# 26D_STEPPER_test.net
KiCad netlist of a schematic drawn in Altium Designer
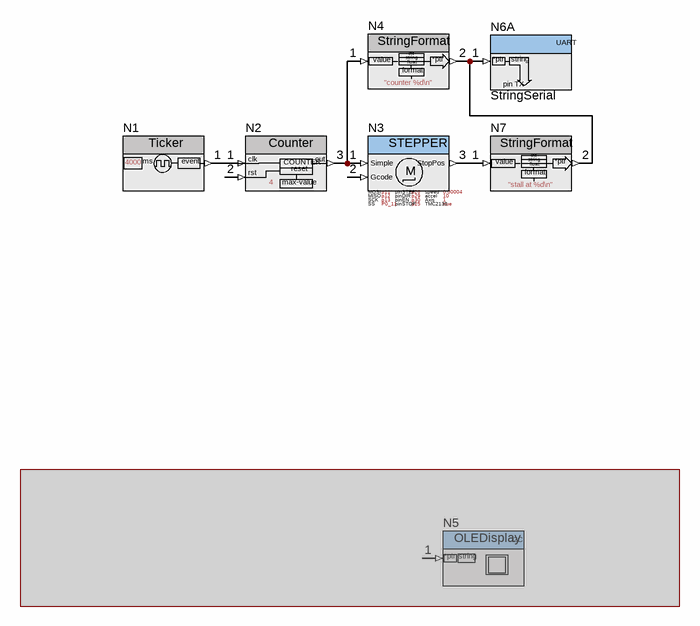
[diagram p0: 26D_STEPPER_test.SchDoc]

(export (version "E")
  (design (tool "Eeschema 10.0.6"))
  (components
    (comp (ref "N1")
      (value "Ticker")
      (description "Creates a Periodical Event")
      (fields (field (name "NBLOCKSPARAMETER1") "4000"))
      (libsource (lib "studio") (part "NODE-TICKER"))
    )
    (comp (ref "N2")
      (value "Counter")
      (fields (field (name "NBLOCKSPARAMETER1") "4"))
      (libsource (lib "studio") (part "NODE-COUNTER"))
    )
    (comp (ref "N3")
      (value "STEPPER")
      (fields
        (field (name "NBLOCKSPARAMETER7") "p30")
        (field (name "NBLOCKSPARAMETER8") "p25")
        (field (name "NBLOCKSPARAMETER9") "0.00004")
        (field (name "NBLOCKSPARAMETER10") "10")
        (field (name "NBLOCKSPARAMETER11") "1")
        (field (name "NBLOCKSPARAMETER12") "true")
        (field (name "PARAMETER 12") "TMC2130")
        (field (name "PARAMETER 11") "Axis")
        (field (name "PARAMETER 10") "accel")
        (field (name "PARAMETER 9") "speed")
        (field (name "PARAMETER 8") "pinSTOP")
        (field (name "PARAMETER 7") "pinEN")
        (field (name "NBLOCKSPARAMETER1") "p11")
        (field (name "NBLOCKSPARAMETER2") "p12")
        (field (name "NBLOCKSPARAMETER3") "p13")
        (field (name "NBLOCKSPARAMETER4") "P0_11")
        (field (name "NBLOCKSPARAMETER5") "p26")
        (field (name "NBLOCKSPARAMETER6") "p29")
        (field (name "PARAMETER 6") "pinDIR")
        (field (name "PARAMETER 5") "pinSTEP")
        (field (name "PARAMETER 2") "MISO")
        (field (name "PARAMETER 1") "MOSI")
        (field (name "PARAMETER 4") "SS")
        (field (name "PARAMETER 3") "SCK")
      )
      (libsource (lib "studio") (part "NODE-STEPPER"))
    )
    (comp (ref "N4")
      (value "StringFormat")
      (fields (field (name "NBLOCKSPARAMETER1") "\"counter %~{d}n\""))
      (libsource (lib "studio") (part "NODE-STRINGFORMAT"))
    )
    (comp (ref "N5") (value "OLEDisplay") (libsource (lib "studio") (part "NODE-OLEDisplay")))
    (comp (ref "N6") (value "StringSerial") (libsource (lib "studio") (part "NODE-STRINGSERIAL-split")))
    (comp (ref "N7")
      (value "StringFormat")
      (fields (field (name "NBLOCKSPARAMETER1") "\"stall at %~{d}n\""))
      (libsource (lib "studio") (part "NODE-STRINGFORMAT"))
    )
  )
  (nets
    (net (code "1") (name "Net-(N1-OUT)") (class "Default")
      (node (ref "N1") (pin "1") (pinfunction "OUT_1") (pintype "output"))
      (node (ref "N2") (pin "1") (pinfunction "COUNT-IN_1") (pintype "input"))
    )
    (net (code "2") (name "Net-(N2-OUT)") (class "Default")
      (node (ref "N2") (pin "3") (pinfunction "OUT_3") (pintype "output"))
      (node (ref "N3") (pin "1") (pinfunction "Simple_1") (pintype "input"))
      (node (ref "N4") (pin "1") (pinfunction "IN_1") (pintype "input"))
    )
    (net (code "3") (name "Net-(N3-StopPos)") (class "Default")
      (node (ref "N3") (pin "3") (pinfunction "StopPos_3") (pintype "output"))
      (node (ref "N7") (pin "1") (pinfunction "IN_1") (pintype "input"))
    )
    (net (code "4") (name "Net-(N4-OUT)") (class "Default")
      (node (ref "N4") (pin "2") (pinfunction "OUT_2") (pintype "output"))
      (node (ref "N6") (pin "1") (pinfunction "TX_1") (pintype "input"))
      (node (ref "N7") (pin "2") (pinfunction "OUT_2") (pintype "output"))
    )
    (net (code "5") (name "unconnected-(N2-RESET-Pad2)") (class "Default")
      (node (ref "N2") (pin "2") (pinfunction "RESET_2") (pintype "input"))
    )
    (net (code "6") (name "unconnected-(N3-Gcode-Pad2)") (class "Default")
      (node (ref "N3") (pin "2") (pinfunction "Gcode_2") (pintype "input"))
    )
    (net (code "7") (name "unconnected-(N5-value-Pad1)") (class "Default")
      (node (ref "N5") (pin "1") (pinfunction "value_1") (pintype "input"))
    )
  )
)
